# Easy_Digi.net
KiCad netlist of a schematic drawn in EAGLE
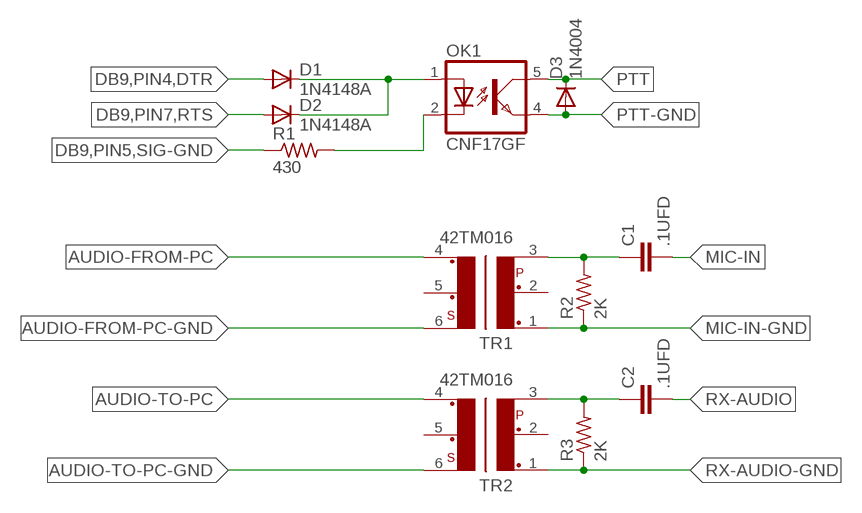
[diagram p0: schematic, sheet 1]

(export (version "E")
  (design (tool "Eeschema 10.0.6"))
  (components
    (comp (ref "C1")
      (value ".1UFD")
      (footprint "eagle-import:C5B3.5")
      (libsource (lib "eagle-import") (part "C5/3.5"))
    )
    (comp (ref "C2")
      (value ".1UFD")
      (footprint "eagle-import:C5B3.5")
      (libsource (lib "eagle-import") (part "C5/3.5"))
    )
    (comp (ref "D1")
      (value "1N4148A")
      (footprint "eagle-import:DO35-10")
      (libsource (lib "eagle-import") (part "1N4148DO35-10"))
    )
    (comp (ref "D2")
      (value "1N4148A")
      (footprint "eagle-import:DO35-10")
      (libsource (lib "eagle-import") (part "1N4148DO35-10"))
    )
    (comp (ref "D3")
      (value "1N4004")
      (footprint "eagle-import:DO41-10")
      (libsource (lib "eagle-import") (part "1N4004"))
    )
    (comp (ref "OK1")
      (value "CNF17GF")
      (footprint "eagle-import:DIL06B")
      (libsource (lib "eagle-import") (part "CNF17GF"))
    )
    (comp (ref "R1")
      (value "430")
      (footprint "eagle-import:0204_7")
      (libsource (lib "eagle-import") (part "R-US_0204/7"))
    )
    (comp (ref "R2")
      (value "2K")
      (footprint "eagle-import:0204_7")
      (libsource (lib "eagle-import") (part "R-US_0204/7"))
    )
    (comp (ref "R3")
      (value "2K")
      (footprint "eagle-import:0204_7")
      (libsource (lib "eagle-import") (part "R-US_0204/7"))
    )
    (comp (ref "TR1")
      (value "42TM016")
      (footprint "eagle-import:42TM")
      (libsource (lib "eagle-import") (part "42T?M016"))
    )
    (comp (ref "TR2")
      (value "42TM016")
      (footprint "eagle-import:42TM")
      (libsource (lib "eagle-import") (part "42T?M016"))
    )
  )
  (nets
    (net (code "1") (name "AUDIO-FROM-PC") (class "Default")
      (node (ref "TR1") (pin "4") (pinfunction "4_4") (pintype "passive"))
    )
    (net (code "2") (name "AUDIO-FROM-PC-GND") (class "Default")
      (node (ref "TR1") (pin "6") (pinfunction "6_6") (pintype "passive"))
    )
    (net (code "3") (name "AUDIO-TO-PC") (class "Default")
      (node (ref "TR2") (pin "4") (pinfunction "4_4") (pintype "passive"))
    )
    (net (code "4") (name "AUDIO-TO-PC-GND") (class "Default")
      (node (ref "TR2") (pin "6") (pinfunction "6_6") (pintype "passive"))
    )
    (net (code "5") (name "DB9,PIN4,DTR") (class "Default")
      (node (ref "D1") (pin "A") (pinfunction "A_A") (pintype "passive"))
    )
    (net (code "6") (name "DB9,PIN5,SIG-GND") (class "Default")
      (node (ref "R1") (pin "1") (pinfunction "1_1") (pintype "passive"))
    )
    (net (code "7") (name "DB9,PIN7,RTS") (class "Default")
      (node (ref "D2") (pin "A") (pinfunction "A_A") (pintype "passive"))
    )
    (net (code "8") (name "MIC-IN") (class "Default")
      (node (ref "C1") (pin "2") (pinfunction "2_2") (pintype "passive"))
    )
    (net (code "9") (name "MIC-IN-GND") (class "Default")
      (node (ref "R2") (pin "1") (pinfunction "1_1") (pintype "passive"))
      (node (ref "TR1") (pin "1") (pinfunction "1_1") (pintype "passive"))
    )
    (net (code "10") (name "Net-(C1-Pad1)") (class "Default")
      (node (ref "C1") (pin "1") (pinfunction "1_1") (pintype "passive"))
      (node (ref "R2") (pin "2") (pinfunction "2_2") (pintype "passive"))
      (node (ref "TR1") (pin "3") (pinfunction "3_3") (pintype "passive"))
    )
    (net (code "11") (name "Net-(C2-Pad1)") (class "Default")
      (node (ref "C2") (pin "1") (pinfunction "1_1") (pintype "passive"))
      (node (ref "R3") (pin "2") (pinfunction "2_2") (pintype "passive"))
      (node (ref "TR2") (pin "3") (pinfunction "3_3") (pintype "passive"))
    )
    (net (code "12") (name "Net-(OK1-A)") (class "Default")
      (node (ref "D1") (pin "C") (pinfunction "C_C") (pintype "passive"))
      (node (ref "D2") (pin "C") (pinfunction "C_C") (pintype "passive"))
      (node (ref "OK1") (pin "1") (pinfunction "A_1") (pintype "passive"))
    )
    (net (code "13") (name "Net-(OK1-C)") (class "Default")
      (node (ref "OK1") (pin "2") (pinfunction "C_2") (pintype "passive"))
      (node (ref "R1") (pin "2") (pinfunction "2_2") (pintype "passive"))
    )
    (net (code "14") (name "PTT") (class "Default")
      (node (ref "D3") (pin "C") (pinfunction "C_C") (pintype "passive"))
      (node (ref "OK1") (pin "5") (pinfunction "COL_5") (pintype "passive"))
    )
    (net (code "15") (name "PTT-GND") (class "Default")
      (node (ref "D3") (pin "A") (pinfunction "A_A") (pintype "passive"))
      (node (ref "OK1") (pin "4") (pinfunction "EMIT_4") (pintype "passive"))
    )
    (net (code "16") (name "RX-AUDIO") (class "Default")
      (node (ref "C2") (pin "2") (pinfunction "2_2") (pintype "passive"))
    )
    (net (code "17") (name "RX-AUDIO-GND") (class "Default")
      (node (ref "R3") (pin "1") (pinfunction "1_1") (pintype "passive"))
      (node (ref "TR2") (pin "1") (pinfunction "1_1") (pintype "passive"))
    )
    (net (code "18") (name "unconnected-(TR1-Pad2)") (class "Default")
      (node (ref "TR1") (pin "2") (pinfunction "2_2") (pintype "passive"))
    )
    (net (code "19") (name "unconnected-(TR1-Pad5)") (class "Default")
      (node (ref "TR1") (pin "5") (pinfunction "5_5") (pintype "passive"))
    )
    (net (code "20") (name "unconnected-(TR2-Pad2)") (class "Default")
      (node (ref "TR2") (pin "2") (pinfunction "2_2") (pintype "passive"))
    )
    (net (code "21") (name "unconnected-(TR2-Pad5)") (class "Default")
      (node (ref "TR2") (pin "5") (pinfunction "5_5") (pintype "passive"))
    )
  )
)
